# audio.net
KiCad netlist of a schematic drawn in Altium Designer
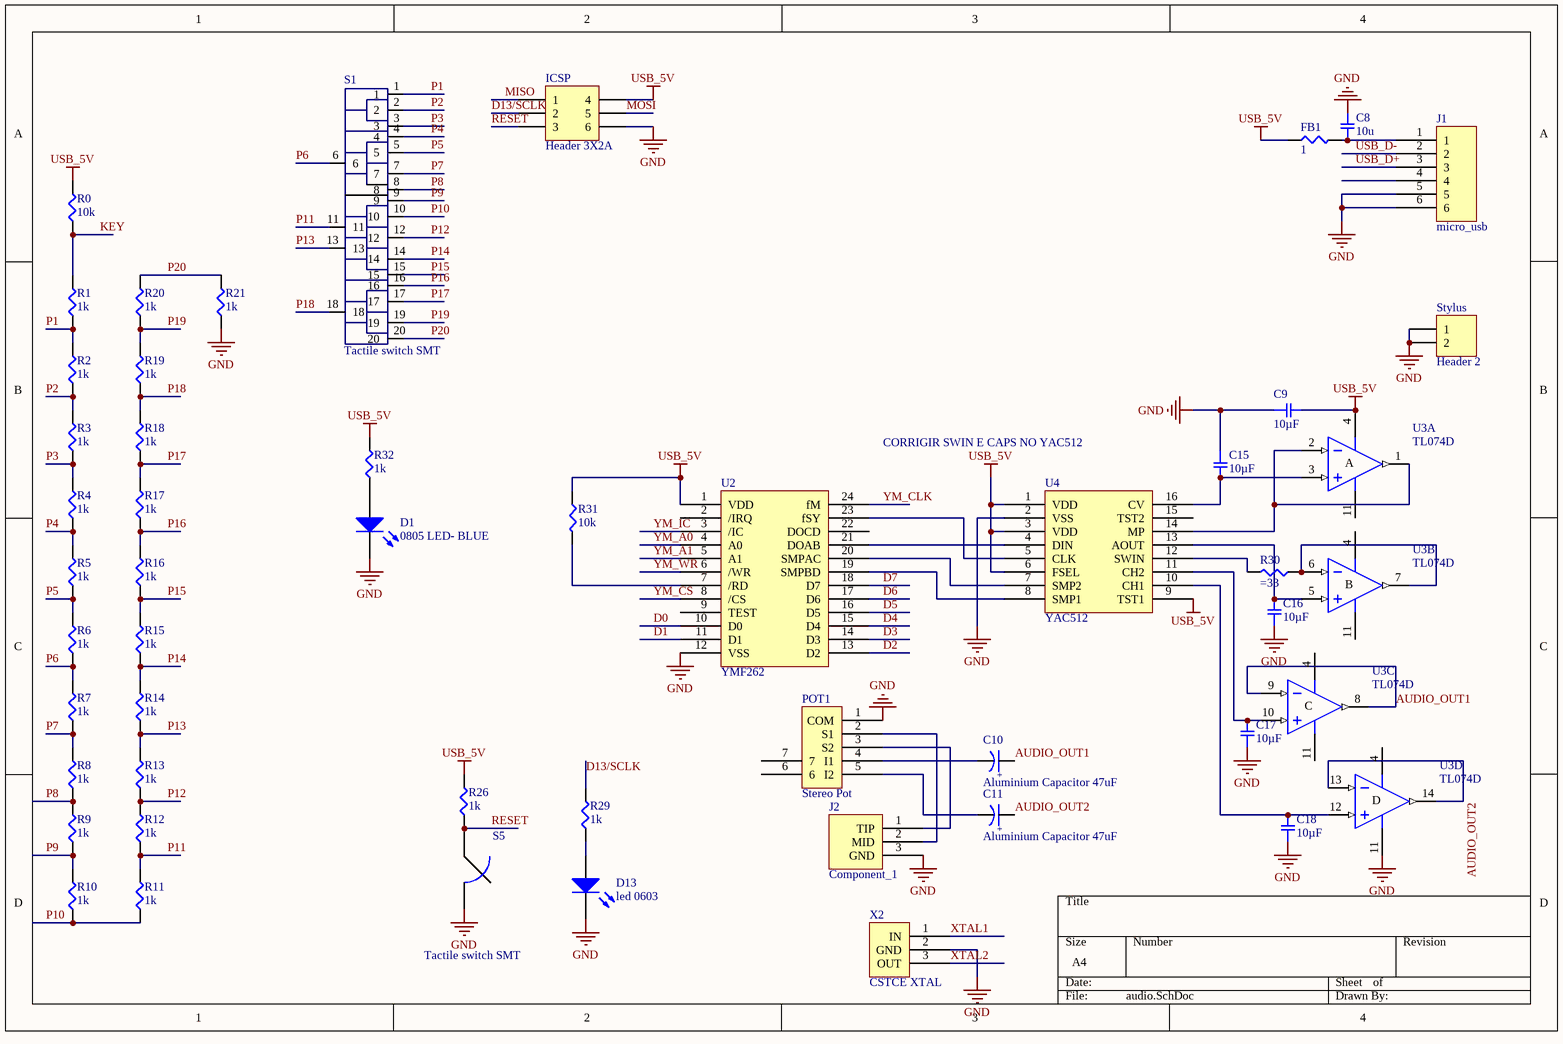
[diagram p0: audio.SchDoc]

(export (version "E")
  (design (tool "Eeschema 10.0.6"))
  (components
    (comp (ref "C8")
      (value "10u")
      (footprint "SMD-0805C")
      (description "CAP CER 10000PF 25V X7R 0805")
      (fields
        (field (name "DIGI-KEY PART NUMBER") "490-12748-1-ND")
        (field (name "PART NUMBER") "GRM216R71E103KA01D")
      )
      (libsource (lib "capacitor_murata_0805") (part "GRM216R71E103KA01D"))
    )
    (comp (ref "C9")
      (value "10µF")
      (footprint "SMD-0805C")
      (description "CAP CER 10UF 6.3V X5R 0805")
      (fields
        (field (name "DIGI-KEY PART NUMBER") "490-3340-1-ND")
        (field (name "PART NUMBER") "GRM219R60J106KE19D")
      )
      (libsource (lib "capacitor_murata_0805") (part "GRM219R60J106KE19D"))
    )
    (comp (ref "C10")
      (value "Aluminium Capacitor 47uF")
      (footprint "Aluminium Capacitor 47uF")
      (libsource (lib "honglong_library") (part "Aluminium Capacitor 47uF"))
    )
    (comp (ref "C11")
      (value "Aluminium Capacitor 47uF")
      (footprint "Aluminium Capacitor 47uF")
      (libsource (lib "honglong_library") (part "Aluminium Capacitor 47uF"))
    )
    (comp (ref "C15")
      (value "10µF")
      (footprint "SMD-0805C")
      (description "CAP CER 10UF 6.3V X5R 0805")
      (fields
        (field (name "DIGI-KEY PART NUMBER") "490-3340-1-ND")
        (field (name "PART NUMBER") "GRM219R60J106KE19D")
      )
      (libsource (lib "capacitor_murata_0805") (part "GRM219R60J106KE19D"))
    )
    (comp (ref "C16")
      (value "10µF")
      (footprint "SMD-0805C")
      (description "CAP CER 10UF 6.3V X5R 0805")
      (fields
        (field (name "DIGI-KEY PART NUMBER") "490-3340-1-ND")
        (field (name "PART NUMBER") "GRM219R60J106KE19D")
      )
      (libsource (lib "capacitor_murata_0805") (part "GRM219R60J106KE19D"))
    )
    (comp (ref "C17")
      (value "10µF")
      (footprint "SMD-0805C")
      (description "CAP CER 10UF 6.3V X5R 0805")
      (fields
        (field (name "DIGI-KEY PART NUMBER") "490-3340-1-ND")
        (field (name "PART NUMBER") "GRM219R60J106KE19D")
      )
      (libsource (lib "capacitor_murata_0805") (part "GRM219R60J106KE19D"))
    )
    (comp (ref "C18")
      (value "10µF")
      (footprint "SMD-0805C")
      (description "CAP CER 10UF 6.3V X5R 0805")
      (fields
        (field (name "DIGI-KEY PART NUMBER") "490-3340-1-ND")
        (field (name "PART NUMBER") "GRM219R60J106KE19D")
      )
      (libsource (lib "capacitor_murata_0805") (part "GRM219R60J106KE19D"))
    )
    (comp (ref "D1")
      (value "0805 LED- BLUE")
      (footprint "0805 LED")
      (libsource (lib "roundie") (part "0805 LED- BLUE"))
    )
    (comp (ref "D13")
      (value "led 0603")
      (footprint "led 0603")
      (libsource (lib "honglong_library") (part "led 0603"))
    )
    (comp (ref "FB1")
      (value "1")
      (footprint "SMD-0603-RES")
      (description "RES SMD 1 OHM 1% 1/4W 0603")
      (fields (field (name "PART NUMBER") "ERJ-3BQF1R0V") (field (name "DIGI-KEY PART NUMBER") "P17371CT-ND"))
      (libsource (lib "Panasonic_ERJ_0603") (part "ERJ-3BQF1R0V"))
    )
    (comp (ref "ICSP")
      (value "Header 3X2A")
      (footprint "HDR2X3_CEN")
      (description "Header, 3-Pin, Dual row")
      (fields (field (name "PUBLISHER") "Altium Limited"))
      (libsource (lib "Miscellaneous Connectors") (part "Header 3X2A"))
    )
    (comp (ref "J1")
      (value "micro_usb")
      (footprint "MICROUSB")
      (description "micro USB Type B")
      (libsource (lib "honglong_library") (part "micro_usb"))
    )
    (comp (ref "J2")
      (value "Component_1")
      (footprint "PCBComponent_1")
      (libsource (lib "slide") (part "Component_1"))
    )
    (comp (ref "POT1")
      (value "Stereo Pot")
      (footprint "stereo_pot")
      (description "Stereo Audio Pot")
      (libsource (lib "slide") (part "Stereo Pot"))
    )
    (comp (ref "R0")
      (value "10k")
      (footprint "SMD-0805-RES")
      (description "RES SMD 1K OHM 1% 1/2W 0805")
      (fields
        (field (name "PART NUMBER") "ERJ-P06F1001V")
        (field (name "DIGI-KEY PART NUMBER") "P16058CT-ND")
      )
      (libsource (lib "Panasonic_ERJ_0805") (part "ERJ-P06F1001V"))
    )
    (comp (ref "R1")
      (value "1k")
      (footprint "SMD-0805-RES")
      (description "RES SMD 1K OHM 1% 1/2W 0805")
      (fields
        (field (name "PART NUMBER") "ERJ-P06F1001V")
        (field (name "DIGI-KEY PART NUMBER") "P16058CT-ND")
      )
      (libsource (lib "Panasonic_ERJ_0805") (part "ERJ-P06F1001V"))
    )
    (comp (ref "R2")
      (value "1k")
      (footprint "SMD-0805-RES")
      (description "RES SMD 1K OHM 1% 1/2W 0805")
      (fields
        (field (name "PART NUMBER") "ERJ-P06F1001V")
        (field (name "DIGI-KEY PART NUMBER") "P16058CT-ND")
      )
      (libsource (lib "Panasonic_ERJ_0805") (part "ERJ-P06F1001V"))
    )
    (comp (ref "R3")
      (value "1k")
      (footprint "SMD-0805-RES")
      (description "RES SMD 1K OHM 1% 1/2W 0805")
      (fields
        (field (name "PART NUMBER") "ERJ-P06F1001V")
        (field (name "DIGI-KEY PART NUMBER") "P16058CT-ND")
      )
      (libsource (lib "Panasonic_ERJ_0805") (part "ERJ-P06F1001V"))
    )
    (comp (ref "R4")
      (value "1k")
      (footprint "SMD-0805-RES")
      (description "RES SMD 1K OHM 1% 1/2W 0805")
      (fields
        (field (name "PART NUMBER") "ERJ-P06F1001V")
        (field (name "DIGI-KEY PART NUMBER") "P16058CT-ND")
      )
      (libsource (lib "Panasonic_ERJ_0805") (part "ERJ-P06F1001V"))
    )
    (comp (ref "R5")
      (value "1k")
      (footprint "SMD-0805-RES")
      (description "RES SMD 1K OHM 1% 1/2W 0805")
      (fields
        (field (name "PART NUMBER") "ERJ-P06F1001V")
        (field (name "DIGI-KEY PART NUMBER") "P16058CT-ND")
      )
      (libsource (lib "Panasonic_ERJ_0805") (part "ERJ-P06F1001V"))
    )
    (comp (ref "R6")
      (value "1k")
      (footprint "SMD-0805-RES")
      (description "RES SMD 1K OHM 1% 1/2W 0805")
      (fields
        (field (name "PART NUMBER") "ERJ-P06F1001V")
        (field (name "DIGI-KEY PART NUMBER") "P16058CT-ND")
      )
      (libsource (lib "Panasonic_ERJ_0805") (part "ERJ-P06F1001V"))
    )
    (comp (ref "R7")
      (value "1k")
      (footprint "SMD-0805-RES")
      (description "RES SMD 1K OHM 1% 1/2W 0805")
      (fields
        (field (name "PART NUMBER") "ERJ-P06F1001V")
        (field (name "DIGI-KEY PART NUMBER") "P16058CT-ND")
      )
      (libsource (lib "Panasonic_ERJ_0805") (part "ERJ-P06F1001V"))
    )
    (comp (ref "R8")
      (value "1k")
      (footprint "SMD-0805-RES")
      (description "RES SMD 1K OHM 1% 1/2W 0805")
      (fields
        (field (name "PART NUMBER") "ERJ-P06F1001V")
        (field (name "DIGI-KEY PART NUMBER") "P16058CT-ND")
      )
      (libsource (lib "Panasonic_ERJ_0805") (part "ERJ-P06F1001V"))
    )
    (comp (ref "R9")
      (value "1k")
      (footprint "SMD-0805-RES")
      (description "RES SMD 1K OHM 1% 1/2W 0805")
      (fields
        (field (name "PART NUMBER") "ERJ-P06F1001V")
        (field (name "DIGI-KEY PART NUMBER") "P16058CT-ND")
      )
      (libsource (lib "Panasonic_ERJ_0805") (part "ERJ-P06F1001V"))
    )
    (comp (ref "R10")
      (value "1k")
      (footprint "SMD-0805-RES")
      (description "RES SMD 1K OHM 1% 1/2W 0805")
      (fields
        (field (name "PART NUMBER") "ERJ-P06F1001V")
        (field (name "DIGI-KEY PART NUMBER") "P16058CT-ND")
      )
      (libsource (lib "Panasonic_ERJ_0805") (part "ERJ-P06F1001V"))
    )
    (comp (ref "R11")
      (value "1k")
      (footprint "SMD-0805-RES")
      (description "RES SMD 1K OHM 1% 1/2W 0805")
      (fields
        (field (name "PART NUMBER") "ERJ-P06F1001V")
        (field (name "DIGI-KEY PART NUMBER") "P16058CT-ND")
      )
      (libsource (lib "Panasonic_ERJ_0805") (part "ERJ-P06F1001V"))
    )
    (comp (ref "R12")
      (value "1k")
      (footprint "SMD-0805-RES")
      (description "RES SMD 1K OHM 1% 1/2W 0805")
      (fields
        (field (name "PART NUMBER") "ERJ-P06F1001V")
        (field (name "DIGI-KEY PART NUMBER") "P16058CT-ND")
      )
      (libsource (lib "Panasonic_ERJ_0805") (part "ERJ-P06F1001V"))
    )
    (comp (ref "R13")
      (value "1k")
      (footprint "SMD-0805-RES")
      (description "RES SMD 1K OHM 1% 1/2W 0805")
      (fields
        (field (name "PART NUMBER") "ERJ-P06F1001V")
        (field (name "DIGI-KEY PART NUMBER") "P16058CT-ND")
      )
      (libsource (lib "Panasonic_ERJ_0805") (part "ERJ-P06F1001V"))
    )
    (comp (ref "R14")
      (value "1k")
      (footprint "SMD-0805-RES")
      (description "RES SMD 1K OHM 1% 1/2W 0805")
      (fields
        (field (name "PART NUMBER") "ERJ-P06F1001V")
        (field (name "DIGI-KEY PART NUMBER") "P16058CT-ND")
      )
      (libsource (lib "Panasonic_ERJ_0805") (part "ERJ-P06F1001V"))
    )
    (comp (ref "R15")
      (value "1k")
      (footprint "SMD-0805-RES")
      (description "RES SMD 1K OHM 1% 1/2W 0805")
      (fields
        (field (name "PART NUMBER") "ERJ-P06F1001V")
        (field (name "DIGI-KEY PART NUMBER") "P16058CT-ND")
      )
      (libsource (lib "Panasonic_ERJ_0805") (part "ERJ-P06F1001V"))
    )
    (comp (ref "R16")
      (value "1k")
      (footprint "SMD-0805-RES")
      (description "RES SMD 1K OHM 1% 1/2W 0805")
      (fields
        (field (name "PART NUMBER") "ERJ-P06F1001V")
        (field (name "DIGI-KEY PART NUMBER") "P16058CT-ND")
      )
      (libsource (lib "Panasonic_ERJ_0805") (part "ERJ-P06F1001V"))
    )
    (comp (ref "R17")
      (value "1k")
      (footprint "SMD-0805-RES")
      (description "RES SMD 1K OHM 1% 1/2W 0805")
      (fields
        (field (name "PART NUMBER") "ERJ-P06F1001V")
        (field (name "DIGI-KEY PART NUMBER") "P16058CT-ND")
      )
      (libsource (lib "Panasonic_ERJ_0805") (part "ERJ-P06F1001V"))
    )
    (comp (ref "R18")
      (value "1k")
      (footprint "SMD-0805-RES")
      (description "RES SMD 1K OHM 1% 1/2W 0805")
      (fields
        (field (name "PART NUMBER") "ERJ-P06F1001V")
        (field (name "DIGI-KEY PART NUMBER") "P16058CT-ND")
      )
      (libsource (lib "Panasonic_ERJ_0805") (part "ERJ-P06F1001V"))
    )
    (comp (ref "R19")
      (value "1k")
      (footprint "SMD-0805-RES")
      (description "RES SMD 1K OHM 1% 1/2W 0805")
      (fields
        (field (name "PART NUMBER") "ERJ-P06F1001V")
        (field (name "DIGI-KEY PART NUMBER") "P16058CT-ND")
      )
      (libsource (lib "Panasonic_ERJ_0805") (part "ERJ-P06F1001V"))
    )
    (comp (ref "R20")
      (value "1k")
      (footprint "SMD-0805-RES")
      (description "RES SMD 1K OHM 1% 1/2W 0805")
      (fields
        (field (name "PART NUMBER") "ERJ-P06F1001V")
        (field (name "DIGI-KEY PART NUMBER") "P16058CT-ND")
      )
      (libsource (lib "Panasonic_ERJ_0805") (part "ERJ-P06F1001V"))
    )
    (comp (ref "R21")
      (value "1k")
      (footprint "SMD-0805-RES")
      (description "RES SMD 1K OHM 1% 1/2W 0805")
      (fields
        (field (name "PART NUMBER") "ERJ-P06F1001V")
        (field (name "DIGI-KEY PART NUMBER") "P16058CT-ND")
      )
      (libsource (lib "Panasonic_ERJ_0805") (part "ERJ-P06F1001V"))
    )
    (comp (ref "R26")
      (value "1k")
      (footprint "SMD-0805-RES")
      (description "RES SMD 1K OHM 1% 1/2W 0805")
      (fields
        (field (name "PART NUMBER") "ERJ-P06F1001V")
        (field (name "DIGI-KEY PART NUMBER") "P16058CT-ND")
      )
      (libsource (lib "Panasonic_ERJ_0805") (part "ERJ-P06F1001V"))
    )
    (comp (ref "R29")
      (value "1k")
      (footprint "SMD-0805-RES")
      (description "RES SMD 1K OHM 1% 1/2W 0805")
      (fields
        (field (name "PART NUMBER") "ERJ-P06F1001V")
        (field (name "DIGI-KEY PART NUMBER") "P16058CT-ND")
      )
      (libsource (lib "Panasonic_ERJ_0805") (part "ERJ-P06F1001V"))
    )
    (comp (ref "R30")
      (value "~")
      (footprint "SMD-0805-RES")
      (description "RES SMD 1K OHM 1% 1/2W 0805")
      (fields
        (field (name "PART NUMBER") "ERJ-P06F1001V")
        (field (name "DIGI-KEY PART NUMBER") "P16058CT-ND")
      )
      (libsource (lib "Panasonic_ERJ_0805") (part "ERJ-P06F1001V"))
    )
    (comp (ref "R31")
      (value "10k")
      (footprint "SMD-0805-RES")
      (description "RES SMD 1K OHM 1% 1/2W 0805")
      (fields
        (field (name "PART NUMBER") "ERJ-P06F1001V")
        (field (name "DIGI-KEY PART NUMBER") "P16058CT-ND")
      )
      (libsource (lib "Panasonic_ERJ_0805") (part "ERJ-P06F1001V"))
    )
    (comp (ref "R32")
      (value "1k")
      (footprint "SMD-0805-RES")
      (description "RES SMD 1K OHM 1% 1/2W 0805")
      (fields
        (field (name "PART NUMBER") "ERJ-P06F1001V")
        (field (name "DIGI-KEY PART NUMBER") "P16058CT-ND")
      )
      (libsource (lib "Panasonic_ERJ_0805") (part "ERJ-P06F1001V"))
    )
    (comp (ref "S1")
      (value "Tactile switch SMT")
      (footprint "left_key")
      (libsource (lib "slide") (part "Tactile switch SMT"))
    )
    (comp (ref "S5")
      (value "Tactile switch SMT")
      (footprint "Tactile switch SMT")
      (libsource (lib "roundie") (part "Tactile switch SMT"))
    )
    (comp (ref "Stylus")
      (value "Header 2")
      (footprint "HDR1X2")
      (description "Header, 2-Pin")
      (fields (field (name "PUBLISHER") "Altium Limited"))
      (libsource (lib "Miscellaneous Connectors") (part "Header 2"))
    )
    (comp (ref "U2")
      (value "YMF262")
      (footprint "ymf262")
      (description "YAMAHA OPL3 YMF262 FM SYNTHESIS")
      (libsource (lib "slide") (part "YMF262"))
    )
    (comp (ref "U3")
      (value "TL074D")
      (footprint "D014_N")
      (description "Low-Noise JFET-Input Operational Amplifier")
      (fields (field (name "PUBLISHER") "Altium Limited"))
      (libsource (lib "TI Operational Amplifier") (part "TL074D"))
    )
    (comp (ref "U4") (value "YAC512") (footprint "YAC512-M") (libsource (lib "slide") (part "YAC512")))
    (comp (ref "X2")
      (value "CSTCE XTAL")
      (footprint "CSTCE-CCM-R0")
      (description "CST XTAL")
      (libsource (lib "slide") (part "CSTCE XTAL"))
    )
  )
  (nets
    (net (code "1") (name "/AUDIO_OUT1") (class "Default")
      (node (ref "C10") (pin "1") (pinfunction "1_1") (pintype "passive"))
      (node (ref "U3") (pin "8") (pinfunction "OUT_8") (pintype "output"))
      (node (ref "U3") (pin "9") (pinfunction "IN-_9") (pintype "input"))
    )
    (net (code "2") (name "/AUDIO_OUT2") (class "Default")
      (node (ref "C11") (pin "1") (pinfunction "1_1") (pintype "passive"))
      (node (ref "U3") (pin "13") (pinfunction "IN-_13") (pintype "input"))
      (node (ref "U3") (pin "14") (pinfunction "OUT_14") (pintype "output"))
    )
    (net (code "3") (name "/D0") (class "Default")
      (node (ref "U2") (pin "10") (pinfunction "D0_10") (pintype "passive"))
    )
    (net (code "4") (name "/D1") (class "Default")
      (node (ref "U2") (pin "11") (pinfunction "D1_11") (pintype "passive"))
    )
    (net (code "5") (name "/D2") (class "Default")
      (node (ref "U2") (pin "13") (pinfunction "D2_13") (pintype "passive"))
    )
    (net (code "6") (name "/D3") (class "Default")
      (node (ref "U2") (pin "14") (pinfunction "D3_14") (pintype "passive"))
    )
    (net (code "7") (name "/D4") (class "Default")
      (node (ref "U2") (pin "15") (pinfunction "D4_15") (pintype "passive"))
    )
    (net (code "8") (name "/D5") (class "Default")
      (node (ref "U2") (pin "16") (pinfunction "D5_16") (pintype "passive"))
    )
    (net (code "9") (name "/D6") (class "Default")
      (node (ref "U2") (pin "17") (pinfunction "D6_17") (pintype "passive"))
    )
    (net (code "10") (name "/D7") (class "Default")
      (node (ref "U2") (pin "18") (pinfunction "D7_18") (pintype "passive"))
    )
    (net (code "11") (name "/D13{slash}SCLK") (class "Default")
      (node (ref "ICSP") (pin "2") (pinfunction "2_2") (pintype "passive"))
      (node (ref "R29") (pin "2") (pinfunction "2_2") (pintype "passive"))
    )
    (net (code "12") (name "/KEY") (class "Default")
      (node (ref "R0") (pin "1") (pinfunction "1_1") (pintype "passive"))
      (node (ref "R1") (pin "2") (pinfunction "2_2") (pintype "passive"))
    )
    (net (code "13") (name "/MISO") (class "Default")
      (node (ref "ICSP") (pin "1") (pinfunction "1_1") (pintype "passive"))
    )
    (net (code "14") (name "/MOSI") (class "Default")
      (node (ref "ICSP") (pin "5") (pinfunction "5_5") (pintype "passive"))
    )
    (net (code "15") (name "/P1") (class "Default")
      (node (ref "R1") (pin "1") (pinfunction "1_1") (pintype "passive"))
      (node (ref "R2") (pin "2") (pinfunction "2_2") (pintype "passive"))
      (node (ref "S1") (pin "1") (pinfunction "1_1") (pintype "passive"))
    )
    (net (code "16") (name "/P2") (class "Default")
      (node (ref "R2") (pin "1") (pinfunction "1_1") (pintype "passive"))
      (node (ref "R3") (pin "2") (pinfunction "2_2") (pintype "passive"))
      (node (ref "S1") (pin "2") (pinfunction "2_2") (pintype "passive"))
    )
    (net (code "17") (name "/P3") (class "Default")
      (node (ref "R3") (pin "1") (pinfunction "1_1") (pintype "passive"))
      (node (ref "R4") (pin "2") (pinfunction "2_2") (pintype "passive"))
      (node (ref "S1") (pin "3") (pinfunction "3_3") (pintype "passive"))
    )
    (net (code "18") (name "/P4") (class "Default")
      (node (ref "R4") (pin "1") (pinfunction "1_1") (pintype "passive"))
      (node (ref "R5") (pin "2") (pinfunction "2_2") (pintype "passive"))
      (node (ref "S1") (pin "4") (pinfunction "4_4") (pintype "passive"))
    )
    (net (code "19") (name "/P5") (class "Default")
      (node (ref "R5") (pin "1") (pinfunction "1_1") (pintype "passive"))
      (node (ref "R6") (pin "2") (pinfunction "2_2") (pintype "passive"))
      (node (ref "S1") (pin "5") (pinfunction "5_5") (pintype "passive"))
    )
    (net (code "20") (name "/P6") (class "Default")
      (node (ref "R6") (pin "1") (pinfunction "1_1") (pintype "passive"))
      (node (ref "R7") (pin "2") (pinfunction "2_2") (pintype "passive"))
      (node (ref "S1") (pin "6") (pinfunction "6_6") (pintype "passive"))
    )
    (net (code "21") (name "/P7") (class "Default")
      (node (ref "R7") (pin "1") (pinfunction "1_1") (pintype "passive"))
      (node (ref "R8") (pin "2") (pinfunction "2_2") (pintype "passive"))
      (node (ref "S1") (pin "7") (pinfunction "7_7") (pintype "passive"))
    )
    (net (code "22") (name "/P8") (class "Default")
      (node (ref "R8") (pin "1") (pinfunction "1_1") (pintype "passive"))
      (node (ref "R9") (pin "2") (pinfunction "2_2") (pintype "passive"))
      (node (ref "S1") (pin "8") (pinfunction "8_8") (pintype "passive"))
    )
    (net (code "23") (name "/P9") (class "Default")
      (node (ref "R10") (pin "2") (pinfunction "2_2") (pintype "passive"))
      (node (ref "R9") (pin "1") (pinfunction "1_1") (pintype "passive"))
      (node (ref "S1") (pin "9") (pinfunction "9_9") (pintype "passive"))
    )
    (net (code "24") (name "/P10") (class "Default")
      (node (ref "R10") (pin "1") (pinfunction "1_1") (pintype "passive"))
      (node (ref "R11") (pin "1") (pinfunction "1_1") (pintype "passive"))
      (node (ref "S1") (pin "10") (pinfunction "10_10") (pintype "passive"))
    )
    (net (code "25") (name "/P11") (class "Default")
      (node (ref "R11") (pin "2") (pinfunction "2_2") (pintype "passive"))
      (node (ref "R12") (pin "1") (pinfunction "1_1") (pintype "passive"))
      (node (ref "S1") (pin "11") (pinfunction "11_11") (pintype "passive"))
    )
    (net (code "26") (name "/P12") (class "Default")
      (node (ref "R12") (pin "2") (pinfunction "2_2") (pintype "passive"))
      (node (ref "R13") (pin "1") (pinfunction "1_1") (pintype "passive"))
      (node (ref "S1") (pin "12") (pinfunction "12_12") (pintype "passive"))
    )
    (net (code "27") (name "/P13") (class "Default")
      (node (ref "R13") (pin "2") (pinfunction "2_2") (pintype "passive"))
      (node (ref "R14") (pin "1") (pinfunction "1_1") (pintype "passive"))
      (node (ref "S1") (pin "13") (pinfunction "13_13") (pintype "passive"))
    )
    (net (code "28") (name "/P14") (class "Default")
      (node (ref "R14") (pin "2") (pinfunction "2_2") (pintype "passive"))
      (node (ref "R15") (pin "1") (pinfunction "1_1") (pintype "passive"))
      (node (ref "S1") (pin "14") (pinfunction "14_14") (pintype "passive"))
    )
    (net (code "29") (name "/P15") (class "Default")
      (node (ref "R15") (pin "2") (pinfunction "2_2") (pintype "passive"))
      (node (ref "R16") (pin "1") (pinfunction "1_1") (pintype "passive"))
      (node (ref "S1") (pin "15") (pinfunction "15_15") (pintype "passive"))
    )
    (net (code "30") (name "/P16") (class "Default")
      (node (ref "R16") (pin "2") (pinfunction "2_2") (pintype "passive"))
      (node (ref "R17") (pin "1") (pinfunction "1_1") (pintype "passive"))
      (node (ref "S1") (pin "16") (pinfunction "16_16") (pintype "passive"))
    )
    (net (code "31") (name "/P17") (class "Default")
      (node (ref "R17") (pin "2") (pinfunction "2_2") (pintype "passive"))
      (node (ref "R18") (pin "1") (pinfunction "1_1") (pintype "passive"))
      (node (ref "S1") (pin "17") (pinfunction "17_17") (pintype "passive"))
    )
    (net (code "32") (name "/P18") (class "Default")
      (node (ref "R18") (pin "2") (pinfunction "2_2") (pintype "passive"))
      (node (ref "R19") (pin "1") (pinfunction "1_1") (pintype "passive"))
      (node (ref "S1") (pin "18") (pinfunction "18_18") (pintype "passive"))
    )
    (net (code "33") (name "/P19") (class "Default")
      (node (ref "R19") (pin "2") (pinfunction "2_2") (pintype "passive"))
      (node (ref "R20") (pin "1") (pinfunction "1_1") (pintype "passive"))
      (node (ref "S1") (pin "19") (pinfunction "19_19") (pintype "passive"))
    )
    (net (code "34") (name "/P20") (class "Default")
      (node (ref "R20") (pin "2") (pinfunction "2_2") (pintype "passive"))
      (node (ref "R21") (pin "2") (pinfunction "2_2") (pintype "passive"))
      (node (ref "S1") (pin "20") (pinfunction "20_20") (pintype "passive"))
    )
    (net (code "35") (name "/RESET") (class "Default")
      (node (ref "ICSP") (pin "3") (pinfunction "3_3") (pintype "passive"))
      (node (ref "R26") (pin "1") (pinfunction "1_1") (pintype "passive"))
      (node (ref "S5") (pin "1") (pinfunction "1_1") (pintype "passive"))
    )
    (net (code "36") (name "/USB_D+") (class "Default")
      (node (ref "J1") (pin "3") (pinfunction "3_3") (pintype "passive"))
    )
    (net (code "37") (name "/USB_D-") (class "Default")
      (node (ref "J1") (pin "2") (pinfunction "2_2") (pintype "passive"))
    )
    (net (code "38") (name "/XTAL1") (class "Default")
      (node (ref "X2") (pin "1") (pinfunction "IN_1") (pintype "passive"))
    )
    (net (code "39") (name "/XTAL2") (class "Default")
      (node (ref "X2") (pin "3") (pinfunction "OUT_3") (pintype "passive"))
    )
    (net (code "40") (name "/YM_A0") (class "Default")
      (node (ref "U2") (pin "4") (pinfunction "A0_4") (pintype "passive"))
    )
    (net (code "41") (name "/YM_A1") (class "Default")
      (node (ref "U2") (pin "5") (pinfunction "A1_5") (pintype "passive"))
    )
    (net (code "42") (name "/YM_CLK") (class "Default")
      (node (ref "U2") (pin "24") (pinfunction "fM_24") (pintype "passive"))
    )
    (net (code "43") (name "/YM_CS") (class "Default")
      (node (ref "U2") (pin "8") (pinfunction "/CS_8") (pintype "passive"))
    )
    (net (code "44") (name "/YM_IC") (class "Default")
      (node (ref "U2") (pin "3") (pinfunction "/IC_3") (pintype "passive"))
    )
    (net (code "45") (name "/YM_WR") (class "Default")
      (node (ref "U2") (pin "6") (pinfunction "/WR_6") (pintype "passive"))
    )
    (net (code "46") (name "GND") (class "Default")
      (node (ref "C15") (pin "1") (pinfunction "1_1") (pintype "passive"))
      (node (ref "C16") (pin "1") (pinfunction "1_1") (pintype "passive"))
      (node (ref "C17") (pin "1") (pinfunction "1_1") (pintype "passive"))
      (node (ref "C18") (pin "1") (pinfunction "1_1") (pintype "passive"))
      (node (ref "C8") (pin "2") (pinfunction "2_2") (pintype "passive"))
      (node (ref "C9") (pin "1") (pinfunction "1_1") (pintype "passive"))
      (node (ref "D1") (pin "2") (pinfunction "K_2") (pintype "passive"))
      (node (ref "D13") (pin "2") (pinfunction "2_2") (pintype "passive"))
      (node (ref "ICSP") (pin "6") (pinfunction "6_6") (pintype "passive"))
      (node (ref "J1") (pin "5") (pinfunction "5_5") (pintype "passive"))
      (node (ref "J1") (pin "6") (pinfunction "6_6") (pintype "passive"))
      (node (ref "J2") (pin "3") (pinfunction "GND_3") (pintype "passive"))
      (node (ref "POT1") (pin "1") (pinfunction "COM_1") (pintype "passive"))
      (node (ref "R21") (pin "1") (pinfunction "1_1") (pintype "passive"))
      (node (ref "S5") (pin "2") (pinfunction "2_2") (pintype "passive"))
      (node (ref "Stylus") (pin "1") (pinfunction "1_1") (pintype "passive"))
      (node (ref "Stylus") (pin "2") (pinfunction "2_2") (pintype "passive"))
      (node (ref "U2") (pin "12") (pinfunction "VSS_12") (pintype "passive"))
      (node (ref "U3") (pin "11") (pinfunction "V-_11") (pintype "power_in"))
      (node (ref "U4") (pin "2") (pinfunction "VSS_2") (pintype "passive"))
      (node (ref "X2") (pin "2") (pinfunction "GND_2") (pintype "passive"))
    )
    (net (code "47") (name "Net-(C8-Pad1)") (class "Default")
      (node (ref "C8") (pin "1") (pinfunction "1_1") (pintype "passive"))
      (node (ref "FB1") (pin "2") (pinfunction "2_2") (pintype "passive"))
      (node (ref "J1") (pin "1") (pinfunction "1_1") (pintype "passive"))
    )
    (net (code "48") (name "Net-(D1-A)") (class "Default")
      (node (ref "D1") (pin "1") (pinfunction "A_1") (pintype "passive"))
      (node (ref "R32") (pin "1") (pinfunction "1_1") (pintype "passive"))
    )
    (net (code "49") (name "Net-(D13-Pad1)") (class "Default")
      (node (ref "D13") (pin "1") (pinfunction "1_1") (pintype "passive"))
      (node (ref "R29") (pin "1") (pinfunction "1_1") (pintype "passive"))
    )
    (net (code "50") (name "Net-(J2-MID)") (class "Default")
      (node (ref "J2") (pin "2") (pinfunction "MID_2") (pintype "passive"))
      (node (ref "POT1") (pin "2") (pinfunction "S1_2") (pintype "passive"))
    )
    (net (code "51") (name "Net-(J2-TIP)") (class "Default")
      (node (ref "J2") (pin "1") (pinfunction "TIP_1") (pintype "passive"))
      (node (ref "POT1") (pin "3") (pinfunction "S2_3") (pintype "passive"))
    )
    (net (code "52") (name "Net-(POT1-I1)") (class "Default")
      (node (ref "C10") (pin "2") (pinfunction "2_2") (pintype "passive"))
      (node (ref "POT1") (pin "4") (pinfunction "I1_4") (pintype "passive"))
    )
    (net (code "53") (name "Net-(POT1-I2)") (class "Default")
      (node (ref "C11") (pin "2") (pinfunction "2_2") (pintype "passive"))
      (node (ref "POT1") (pin "5") (pinfunction "I2_5") (pintype "passive"))
    )
    (net (code "54") (name "Net-(U2-DOAB)") (class "Default")
      (node (ref "U2") (pin "21") (pinfunction "DOAB_21") (pintype "passive"))
      (node (ref "U4") (pin "4") (pinfunction "DIN_4") (pintype "passive"))
    )
    (net (code "55") (name "Net-(U2-SMPAC)") (class "Default")
      (node (ref "U2") (pin "20") (pinfunction "SMPAC_20") (pintype "passive"))
      (node (ref "U4") (pin "7") (pinfunction "SMP2_7") (pintype "passive"))
    )
    (net (code "56") (name "Net-(U2-SMPBD)") (class "Default")
      (node (ref "U2") (pin "19") (pinfunction "SMPBD_19") (pintype "passive"))
      (node (ref "U4") (pin "8") (pinfunction "SMP1_8") (pintype "passive"))
    )
    (net (code "57") (name "Net-(U2-fSY)") (class "Default")
      (node (ref "U2") (pin "23") (pinfunction "fSY_23") (pintype "passive"))
      (node (ref "U4") (pin "5") (pinfunction "CLK_5") (pintype "passive"))
    )
    (net (code "58") (name "Net-(U2-{slash}RD)") (class "Default")
      (node (ref "R31") (pin "2") (pinfunction "2_2") (pintype "passive"))
      (node (ref "U2") (pin "7") (pinfunction "/RD_7") (pintype "passive"))
    )
    (net (code "59") (name "Net-(U3A-IN+)") (class "Default")
      (node (ref "C15") (pin "2") (pinfunction "2_2") (pintype "passive"))
      (node (ref "U3") (pin "3") (pinfunction "IN+_3") (pintype "input"))
      (node (ref "U4") (pin "16") (pinfunction "CV_16") (pintype "passive"))
    )
    (net (code "60") (name "Net-(U3A-IN-)") (class "Default")
      (node (ref "U3") (pin "1") (pinfunction "OUT_1") (pintype "output"))
      (node (ref "U3") (pin "2") (pinfunction "IN-_2") (pintype "input"))
      (node (ref "U4") (pin "14") (pinfunction "MP_14") (pintype "passive"))
    )
    (net (code "61") (name "Net-(U3B-IN+)") (class "Default")
      (node (ref "C16") (pin "2") (pinfunction "2_2") (pintype "passive"))
      (node (ref "U3") (pin "5") (pinfunction "IN+_5") (pintype "input"))
      (node (ref "U4") (pin "13") (pinfunction "AOUT_13") (pintype "passive"))
    )
    (net (code "62") (name "Net-(U3B-IN-)") (class "Default")
      (node (ref "R30") (pin "1") (pinfunction "1_1") (pintype "passive"))
      (node (ref "U3") (pin "6") (pinfunction "IN-_6") (pintype "input"))
      (node (ref "U3") (pin "7") (pinfunction "OUT_7") (pintype "output"))
    )
    (net (code "63") (name "Net-(U3C-IN+)") (class "Default")
      (node (ref "C17") (pin "2") (pinfunction "2_2") (pintype "passive"))
      (node (ref "U3") (pin "10") (pinfunction "IN+_10") (pintype "input"))
      (node (ref "U4") (pin "11") (pinfunction "CH2_11") (pintype "passive"))
    )
    (net (code "64") (name "Net-(U3D-IN+)") (class "Default")
      (node (ref "C18") (pin "2") (pinfunction "2_2") (pintype "passive"))
      (node (ref "U3") (pin "12") (pinfunction "IN+_12") (pintype "input"))
      (node (ref "U4") (pin "10") (pinfunction "CH1_10") (pintype "passive"))
    )
    (net (code "65") (name "Net-(U4-SWIN)") (class "Default")
      (node (ref "R30") (pin "2") (pinfunction "2_2") (pintype "passive"))
      (node (ref "U4") (pin "12") (pinfunction "SWIN_12") (pintype "passive"))
    )
    (net (code "66") (name "USB_5V") (class "Default")
      (node (ref "C9") (pin "2") (pinfunction "2_2") (pintype "passive"))
      (node (ref "FB1") (pin "1") (pinfunction "1_1") (pintype "passive"))
      (node (ref "ICSP") (pin "4") (pinfunction "4_4") (pintype "passive"))
      (node (ref "R0") (pin "2") (pinfunction "2_2") (pintype "passive"))
      (node (ref "R26") (pin "2") (pinfunction "2_2") (pintype "passive"))
      (node (ref "R31") (pin "1") (pinfunction "1_1") (pintype "passive"))
      (node (ref "R32") (pin "2") (pinfunction "2_2") (pintype "passive"))
      (node (ref "U2") (pin "1") (pinfunction "VDD_1") (pintype "passive"))
      (node (ref "U3") (pin "4") (pinfunction "V+_4") (pintype "power_in"))
      (node (ref "U4") (pin "1") (pinfunction "VDD_1") (pintype "passive"))
      (node (ref "U4") (pin "3") (pinfunction "VDD_3") (pintype "passive"))
      (node (ref "U4") (pin "6") (pinfunction "FSEL_6") (pintype "passive"))
      (node (ref "U4") (pin "9") (pinfunction "TST1_9") (pintype "passive"))
    )
    (net (code "67") (name "unconnected-(J1-Pad4)") (class "Default")
      (node (ref "J1") (pin "4") (pinfunction "4_4") (pintype "passive"))
    )
    (net (code "68") (name "unconnected-(POT1-Pad6)") (class "Default")
      (node (ref "POT1") (pin "6") (pinfunction "6_6") (pintype "passive"))
    )
    (net (code "69") (name "unconnected-(POT1-Pad7)") (class "Default")
      (node (ref "POT1") (pin "7") (pinfunction "7_7") (pintype "passive"))
    )
    (net (code "70") (name "unconnected-(U2-DOCD-Pad22)") (class "Default")
      (node (ref "U2") (pin "22") (pinfunction "DOCD_22") (pintype "passive"))
    )
    (net (code "71") (name "unconnected-(U2-TEST-Pad9)") (class "Default")
      (node (ref "U2") (pin "9") (pinfunction "TEST_9") (pintype "passive"))
    )
    (net (code "72") (name "unconnected-(U2-{slash}IRQ-Pad2)") (class "Default")
      (node (ref "U2") (pin "2") (pinfunction "/IRQ_2") (pintype "passive"))
    )
    (net (code "73") (name "unconnected-(U3A-V--Pad11)") (class "Default")
      (node (ref "U3") (pin "11") (pinfunction "V-_11") (pintype "power_in"))
    )
    (net (code "74") (name "unconnected-(U3B-V+-Pad4)") (class "Default")
      (node (ref "U3") (pin "4") (pinfunction "V+_4") (pintype "power_in"))
    )
    (net (code "75") (name "unconnected-(U3B-V--Pad11)") (class "Default")
      (node (ref "U3") (pin "11") (pinfunction "V-_11") (pintype "power_in"))
    )
    (net (code "76") (name "unconnected-(U3C-V+-Pad4)") (class "Default")
      (node (ref "U3") (pin "4") (pinfunction "V+_4") (pintype "power_in"))
    )
    (net (code "77") (name "unconnected-(U3C-V--Pad11)") (class "Default")
      (node (ref "U3") (pin "11") (pinfunction "V-_11") (pintype "power_in"))
    )
    (net (code "78") (name "unconnected-(U3D-V+-Pad4)") (class "Default")
      (node (ref "U3") (pin "4") (pinfunction "V+_4") (pintype "power_in"))
    )
    (net (code "79") (name "unconnected-(U4-TST2-Pad15)") (class "Default")
      (node (ref "U4") (pin "15") (pinfunction "TST2_15") (pintype "passive"))
    )
  )
)
